# 09_Power_LDO.net
KiCad netlist of a schematic drawn in Altium Designer
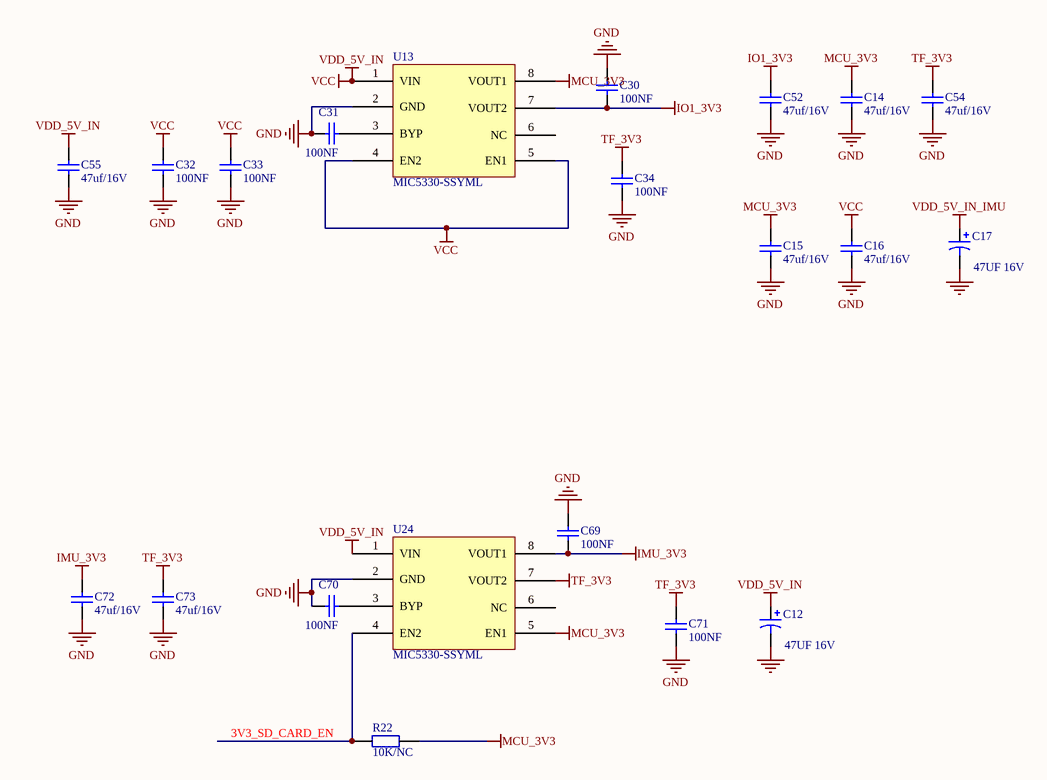
[diagram p0: 09_Power_LDO.SchDoc]

(export (version "E")
  (design (tool "Eeschema 10.0.6"))
  (components
    (comp (ref "C12")
      (value "47UF 16V")
      (footprint "7343CAP")
      (description "T520V476M016ATE")
      (fields (field (name "PUBLISHER") "Altium Limited"))
      (libsource (lib "Miscellaneous Devices") (part "Cap Pol1"))
    )
    (comp (ref "C14")
      (value "47uf/16V")
      (description "Capacitor")
      (libsource (lib "Miscellaneous Devices") (part "Cap"))
    )
    (comp (ref "C15")
      (value "47uf/16V")
      (description "Capacitor")
      (libsource (lib "Miscellaneous Devices") (part "Cap"))
    )
    (comp (ref "C16")
      (value "47uf/16V")
      (description "Capacitor")
      (libsource (lib "Miscellaneous Devices") (part "Cap"))
    )
    (comp (ref "C17")
      (value "47UF 16V")
      (footprint "7343CAP")
      (description "T520V476M016ATE")
      (fields (field (name "PUBLISHER") "Altium Limited"))
      (libsource (lib "Miscellaneous Devices") (part "Cap Pol1"))
    )
    (comp (ref "C30")
      (value "100NF")
      (fields (field (name "PUBLISHER") "Altium Limited"))
      (libsource (lib "Miscellaneous Devices") (part "Cap"))
    )
    (comp (ref "C31")
      (value "100NF")
      (fields (field (name "PUBLISHER") "Altium Limited"))
      (libsource (lib "Miscellaneous Devices") (part "Cap"))
    )
    (comp (ref "C32")
      (value "100NF")
      (fields (field (name "PUBLISHER") "Altium Limited"))
      (libsource (lib "Miscellaneous Devices") (part "Cap"))
    )
    (comp (ref "C33")
      (value "100NF")
      (fields (field (name "PUBLISHER") "Altium Limited"))
      (libsource (lib "Miscellaneous Devices") (part "Cap"))
    )
    (comp (ref "C34") (value "100NF") (libsource (lib "Miscellaneous Devices") (part "Cap")))
    (comp (ref "C52")
      (value "47uf/16V")
      (description "Capacitor")
      (libsource (lib "Miscellaneous Devices") (part "Cap"))
    )
    (comp (ref "C54")
      (value "47uf/16V")
      (description "Capacitor")
      (libsource (lib "Miscellaneous Devices") (part "Cap"))
    )
    (comp (ref "C55")
      (value "47uf/16V")
      (description "Capacitor")
      (libsource (lib "Miscellaneous Devices") (part "Cap"))
    )
    (comp (ref "C69")
      (value "100NF")
      (fields (field (name "PUBLISHER") "Altium Limited"))
      (libsource (lib "Miscellaneous Devices") (part "Cap"))
    )
    (comp (ref "C70")
      (value "100NF")
      (fields (field (name "PUBLISHER") "Altium Limited"))
      (libsource (lib "Miscellaneous Devices") (part "Cap"))
    )
    (comp (ref "C71") (value "100NF") (libsource (lib "Miscellaneous Devices") (part "Cap")))
    (comp (ref "C72")
      (value "47uf/16V")
      (description "Capacitor")
      (libsource (lib "Miscellaneous Devices") (part "Cap"))
    )
    (comp (ref "C73")
      (value "47uf/16V")
      (description "Capacitor")
      (libsource (lib "Miscellaneous Devices") (part "Cap"))
    )
    (comp (ref "R22")
      (value "10K/NC")
      (footprint "0402R")
      (description "0402R10K 1%")
      (libsource (lib "CUAV") (part "0402R10K"))
    )
    (comp (ref "U13") (value "MIC5330-SSYML") (footprint "MIC5530") (libsource (lib "hack") (part "MIC5530")))
    (comp (ref "U24") (value "MIC5330-SSYML") (footprint "MIC5530") (libsource (lib "hack") (part "MIC5530")))
  )
  (nets
    (net (code "1") (name "/3V3_SD_CARD_EN") (class "Default")
      (node (ref "R22") (pin "2") (pintype "passive"))
      (node (ref "U24") (pin "4") (pinfunction "EN2_4") (pintype "passive"))
    )
    (net (code "2") (name "GND") (class "Default")
      (node (ref "C12") (pin "C") (pinfunction "2_C") (pintype "passive"))
      (node (ref "C14") (pin "2") (pinfunction "2_2") (pintype "passive"))
      (node (ref "C15") (pin "2") (pinfunction "2_2") (pintype "passive"))
      (node (ref "C16") (pin "2") (pinfunction "2_2") (pintype "passive"))
      (node (ref "C17") (pin "C") (pinfunction "2_C") (pintype "passive"))
      (node (ref "C30") (pin "2") (pinfunction "2_2") (pintype "passive"))
      (node (ref "C31") (pin "2") (pinfunction "2_2") (pintype "passive"))
      (node (ref "C32") (pin "1") (pinfunction "1_1") (pintype "passive"))
      (node (ref "C33") (pin "1") (pinfunction "1_1") (pintype "passive"))
      (node (ref "C34") (pin "1") (pinfunction "1_1") (pintype "passive"))
      (node (ref "C52") (pin "2") (pinfunction "2_2") (pintype "passive"))
      (node (ref "C54") (pin "2") (pinfunction "2_2") (pintype "passive"))
      (node (ref "C55") (pin "2") (pinfunction "2_2") (pintype "passive"))
      (node (ref "C69") (pin "2") (pinfunction "2_2") (pintype "passive"))
      (node (ref "C70") (pin "2") (pinfunction "2_2") (pintype "passive"))
      (node (ref "C71") (pin "1") (pinfunction "1_1") (pintype "passive"))
      (node (ref "C72") (pin "2") (pinfunction "2_2") (pintype "passive"))
      (node (ref "C73") (pin "2") (pinfunction "2_2") (pintype "passive"))
      (node (ref "U13") (pin "2") (pinfunction "GND_2") (pintype "passive"))
      (node (ref "U24") (pin "2") (pinfunction "GND_2") (pintype "passive"))
    )
    (net (code "3") (name "IMU_3V3") (class "Default")
      (node (ref "C69") (pin "1") (pinfunction "1_1") (pintype "passive"))
      (node (ref "C72") (pin "1") (pinfunction "1_1") (pintype "passive"))
      (node (ref "U24") (pin "8") (pinfunction "VOUT1_8") (pintype "passive"))
    )
    (net (code "4") (name "IO1_3V3") (class "Default")
      (node (ref "C30") (pin "1") (pinfunction "1_1") (pintype "passive"))
      (node (ref "C52") (pin "1") (pinfunction "1_1") (pintype "passive"))
      (node (ref "U13") (pin "7") (pinfunction "VOUT2_7") (pintype "passive"))
    )
    (net (code "5") (name "MCU_3V3") (class "Default")
      (node (ref "C14") (pin "1") (pinfunction "1_1") (pintype "passive"))
      (node (ref "C15") (pin "1") (pinfunction "1_1") (pintype "passive"))
      (node (ref "R22") (pin "1") (pintype "passive"))
      (node (ref "U13") (pin "8") (pinfunction "VOUT1_8") (pintype "passive"))
      (node (ref "U24") (pin "5") (pinfunction "EN1_5") (pintype "passive"))
    )
    (net (code "6") (name "Net-(U13-BYP)") (class "Default")
      (node (ref "C31") (pin "1") (pinfunction "1_1") (pintype "passive"))
      (node (ref "U13") (pin "3") (pinfunction "BYP_3") (pintype "passive"))
    )
    (net (code "7") (name "Net-(U24-BYP)") (class "Default")
      (node (ref "C70") (pin "1") (pinfunction "1_1") (pintype "passive"))
      (node (ref "U24") (pin "3") (pinfunction "BYP_3") (pintype "passive"))
    )
    (net (code "8") (name "TF_3V3") (class "Default")
      (node (ref "C34") (pin "2") (pinfunction "2_2") (pintype "passive"))
      (node (ref "C54") (pin "1") (pinfunction "1_1") (pintype "passive"))
      (node (ref "C71") (pin "2") (pinfunction "2_2") (pintype "passive"))
      (node (ref "C73") (pin "1") (pinfunction "1_1") (pintype "passive"))
      (node (ref "U24") (pin "7") (pinfunction "VOUT2_7") (pintype "passive"))
    )
    (net (code "9") (name "VCC") (class "Default")
      (node (ref "C12") (pin "A") (pinfunction "1_A") (pintype "passive"))
      (node (ref "C16") (pin "1") (pinfunction "1_1") (pintype "passive"))
      (node (ref "C32") (pin "2") (pinfunction "2_2") (pintype "passive"))
      (node (ref "C33") (pin "2") (pinfunction "2_2") (pintype "passive"))
      (node (ref "C55") (pin "1") (pinfunction "1_1") (pintype "passive"))
      (node (ref "U13") (pin "1") (pinfunction "VIN_1") (pintype "passive"))
      (node (ref "U13") (pin "4") (pinfunction "EN2_4") (pintype "passive"))
      (node (ref "U13") (pin "5") (pinfunction "EN1_5") (pintype "passive"))
      (node (ref "U24") (pin "1") (pinfunction "VIN_1") (pintype "passive"))
    )
    (net (code "10") (name "VDD_5V_IN_IMU") (class "Default")
      (node (ref "C17") (pin "A") (pinfunction "1_A") (pintype "passive"))
    )
    (net (code "11") (name "unconnected-(U13-NC-Pad6)") (class "Default")
      (node (ref "U13") (pin "6") (pinfunction "NC_6") (pintype "passive"))
    )
    (net (code "12") (name "unconnected-(U24-NC-Pad6)") (class "Default")
      (node (ref "U24") (pin "6") (pinfunction "NC_6") (pintype "passive"))
    )
  )
)
